# Lighting_Controller.net
KiCad netlist of a schematic drawn in EAGLE
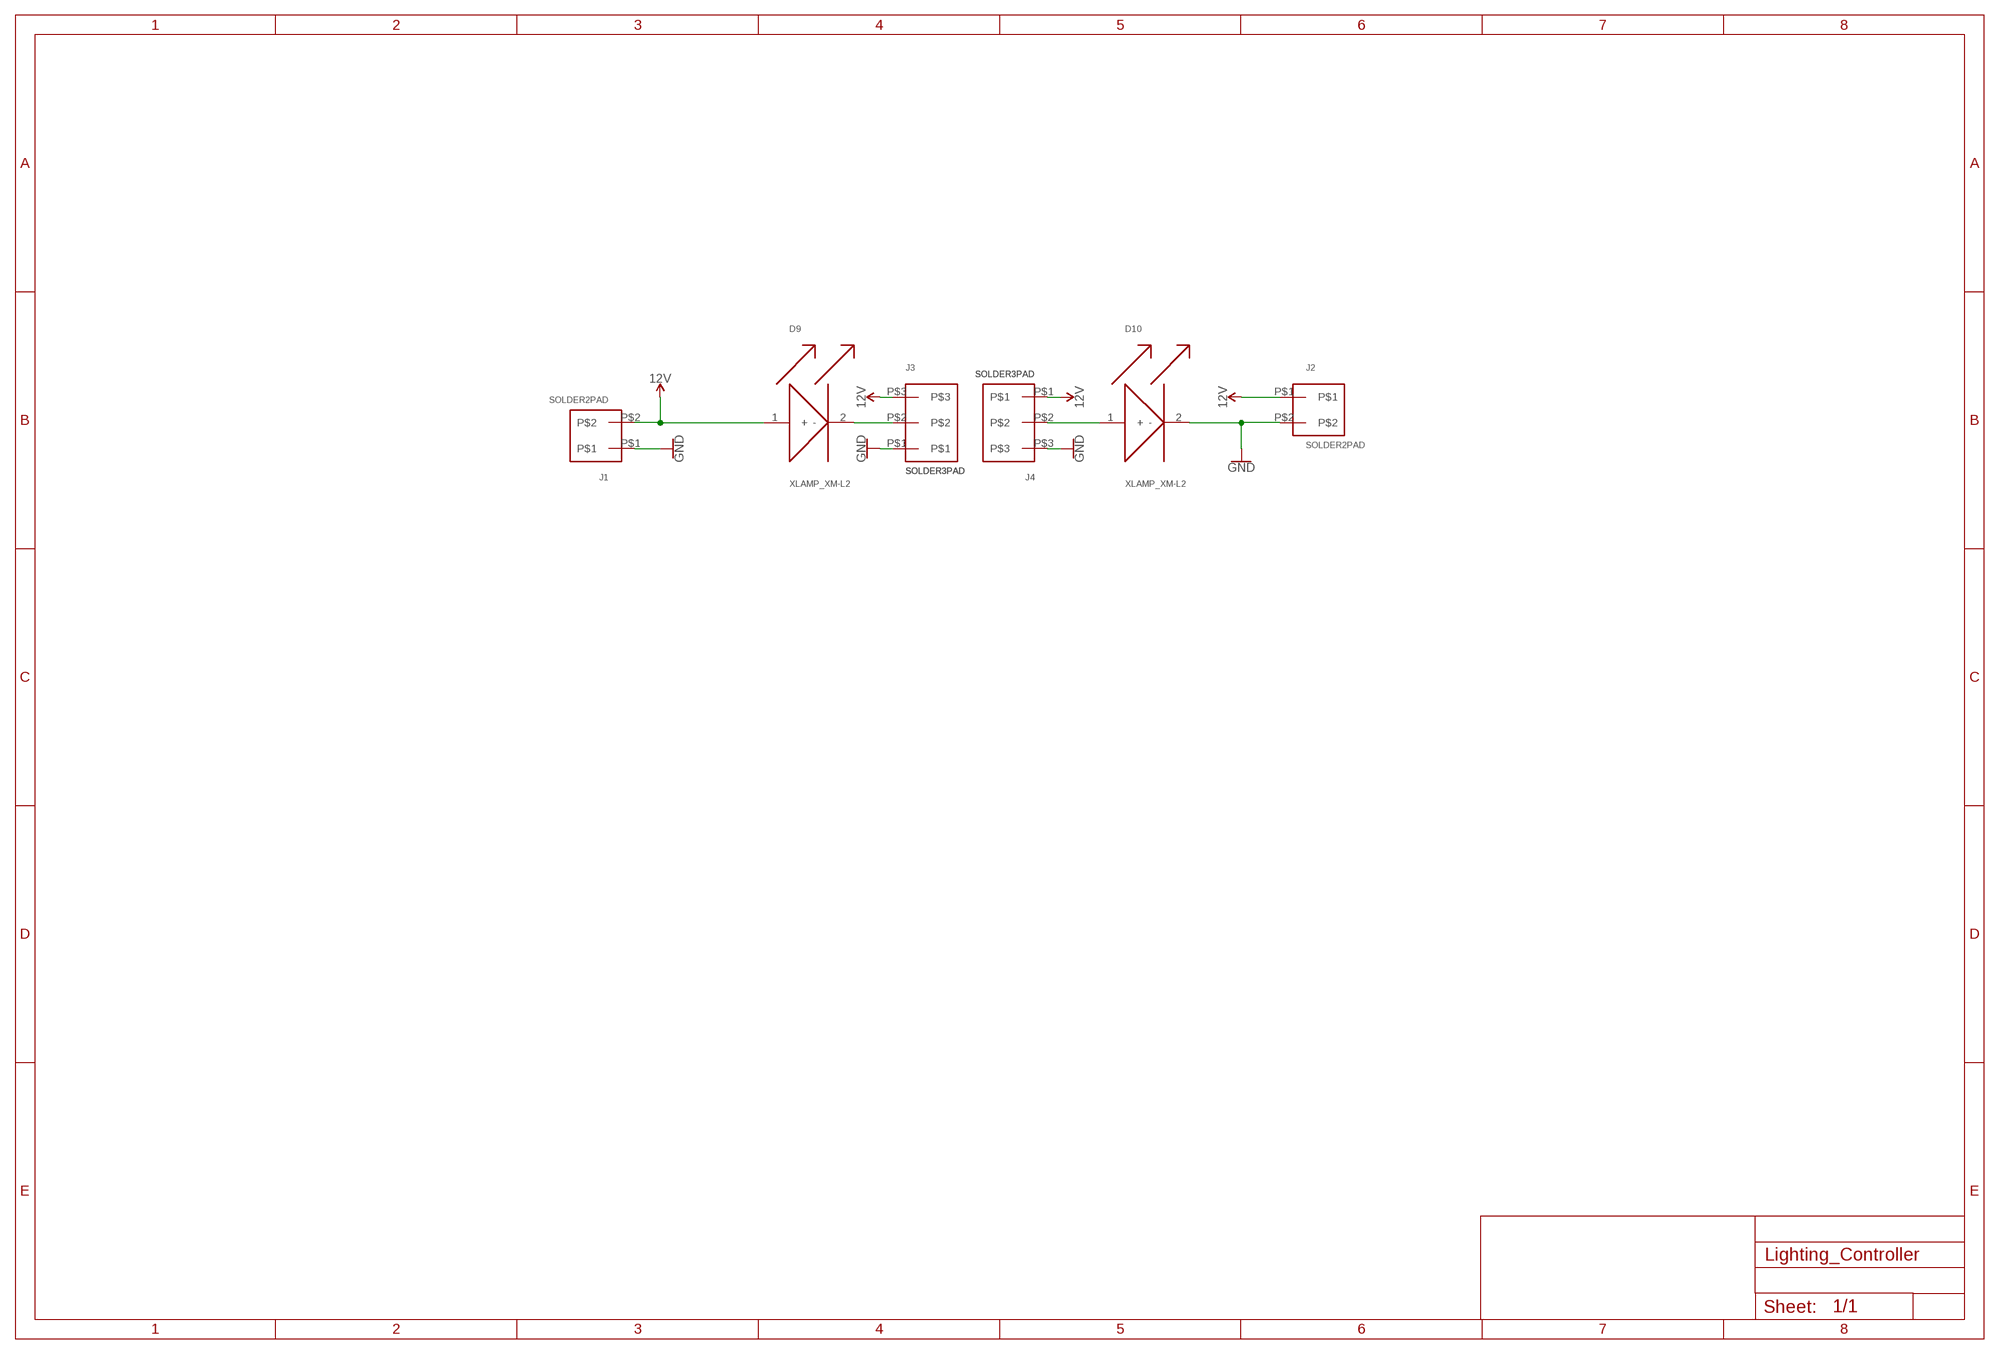
[diagram p0: schematic, sheet 1]

(export (version "E")
  (design (tool "Eeschema 10.0.6"))
  (components
    (comp (ref "D9")
      (value "XLAMP_XM-L2")
      (footprint "eagle-import:XLAMP_XM-L2")
      (libsource (lib "eagle-import") (part "XLAMP_XM-L2"))
    )
    (comp (ref "D10")
      (value "XLAMP_XM-L2")
      (footprint "eagle-import:XLAMP_XM-L2")
      (libsource (lib "eagle-import") (part "XLAMP_XM-L2"))
    )
    (comp (ref "J1")
      (value "SOLDER2PAD")
      (footprint "eagle-import:SOLDER2PAD")
      (libsource (lib "eagle-import") (part "SOLDER2PAD"))
    )
    (comp (ref "J2")
      (value "SOLDER2PAD")
      (footprint "eagle-import:SOLDER2PAD")
      (libsource (lib "eagle-import") (part "SOLDER2PAD"))
    )
    (comp (ref "J3")
      (value "SOLDER3PAD")
      (footprint "eagle-import:SOLDER3PAD")
      (libsource (lib "eagle-import") (part "SOLDER3PAD"))
    )
    (comp (ref "J4")
      (value "SOLDER3PAD")
      (footprint "eagle-import:SOLDER3PAD")
      (libsource (lib "eagle-import") (part "SOLDER3PAD"))
    )
  )
  (nets
    (net (code "1") (name "12V") (class "Default")
      (node (ref "D9") (pin "1") (pinfunction "+_1") (pintype "bidirectional"))
      (node (ref "J1") (pin "P$2") (pinfunction "P$2_P$2") (pintype "bidirectional"))
      (node (ref "J2") (pin "P$1") (pinfunction "P$1_P$1") (pintype "bidirectional"))
      (node (ref "J3") (pin "P$3") (pinfunction "P$3_P$3") (pintype "bidirectional"))
      (node (ref "J4") (pin "P$1") (pinfunction "P$1_P$1") (pintype "bidirectional"))
    )
    (net (code "2") (name "GND") (class "Default")
      (node (ref "D10") (pin "2") (pinfunction "-_2") (pintype "bidirectional"))
      (node (ref "J1") (pin "P$1") (pinfunction "P$1_P$1") (pintype "bidirectional"))
      (node (ref "J2") (pin "P$2") (pinfunction "P$2_P$2") (pintype "bidirectional"))
      (node (ref "J3") (pin "P$1") (pinfunction "P$1_P$1") (pintype "bidirectional"))
      (node (ref "J4") (pin "P$3") (pinfunction "P$3_P$3") (pintype "bidirectional"))
    )
    (net (code "3") (name "Net-(D9--)") (class "Default")
      (node (ref "D9") (pin "2") (pinfunction "-_2") (pintype "bidirectional"))
      (node (ref "J3") (pin "P$2") (pinfunction "P$2_P$2") (pintype "bidirectional"))
    )
    (net (code "4") (name "Net-(D10-+)") (class "Default")
      (node (ref "D10") (pin "1") (pinfunction "+_1") (pintype "bidirectional"))
      (node (ref "J4") (pin "P$2") (pinfunction "P$2_P$2") (pintype "bidirectional"))
    )
  )
)
